# LiPoBattery.net
KiCad netlist of a schematic drawn in Altium Designer
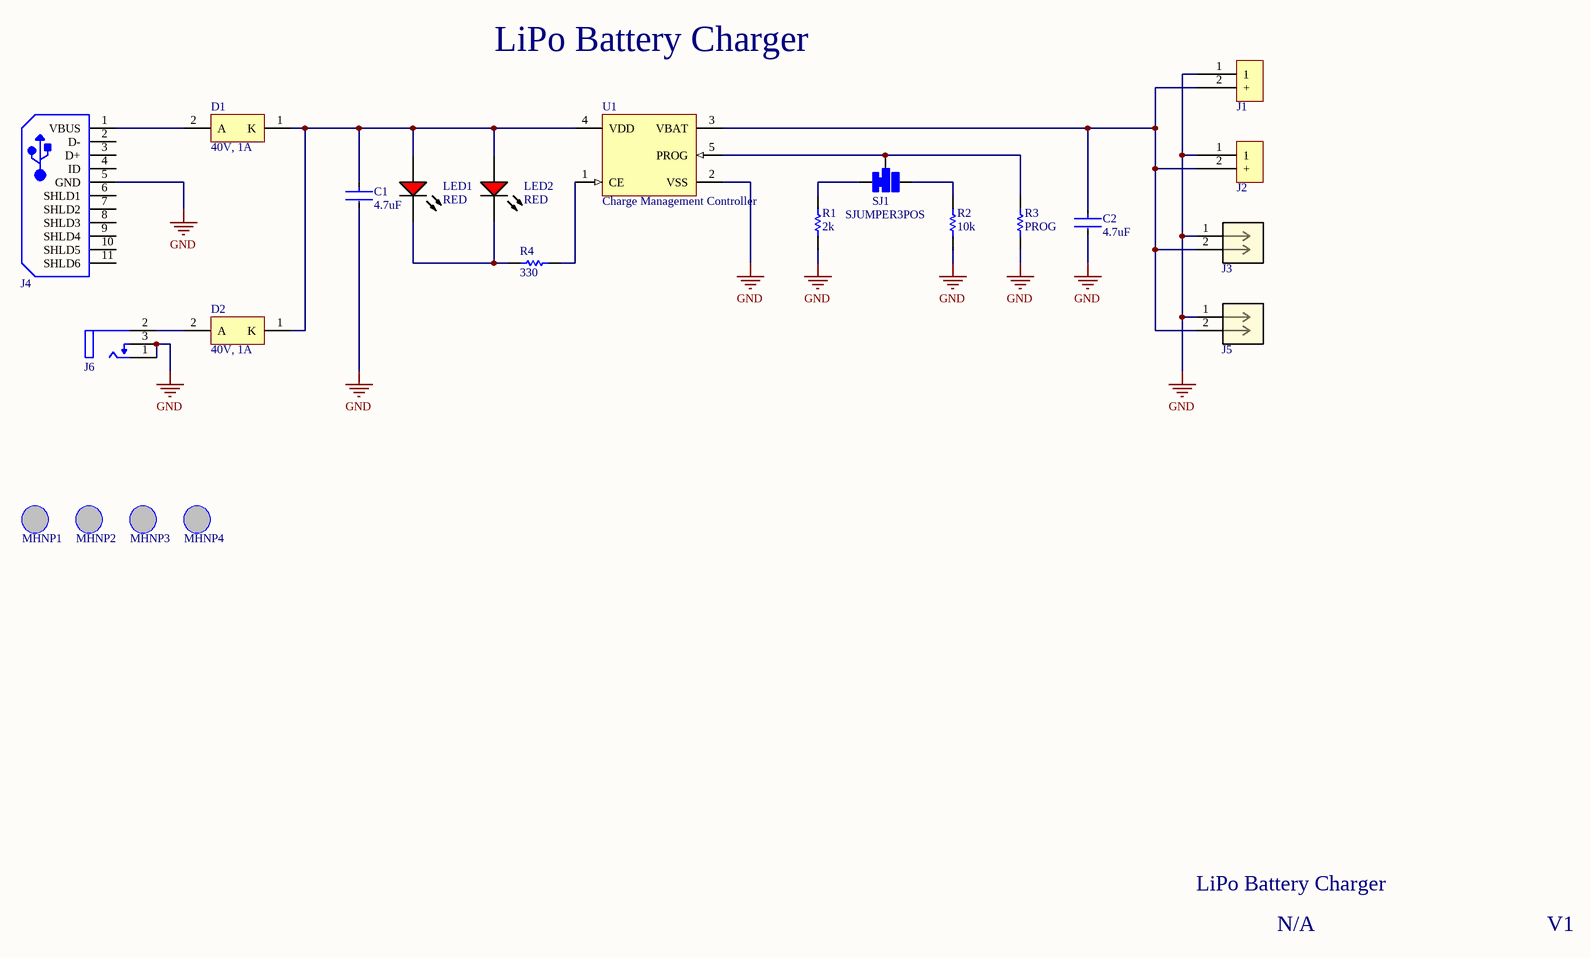
[diagram p0: LiPoBattery.SchDoc]

(export (version "E")
  (design (tool "Eeschema 10.0.6"))
  (components
    (comp (ref "C1")
      (value "4.7uF")
      (footprint "FP-CC0805-0_85-MFG")
      (description "4.7µF ±10% 6.3V Ceramic Capacitor X7R 0805 (2012 Metric)")
      (fields (field (name "MANUFACTURER") "Yageo") (field (name "TOLERANCE") "0.1"))
      (libsource (lib "LiPoBattery_A") (part "CAP CER 4.7UF 6.3V X7R 0805"))
    )
    (comp (ref "C2")
      (value "4.7uF")
      (footprint "FP-CC0805-0_85-MFG")
      (description "4.7µF ±10% 6.3V Ceramic Capacitor X7R 0805 (2012 Metric)")
      (fields (field (name "MANUFACTURER") "Yageo") (field (name "TOLERANCE") "0.1"))
      (libsource (lib "LiPoBattery_A") (part "CAP CER 4.7UF 6.3V X7R 0805"))
    )
    (comp (ref "D1")
      (value "40V, 1A")
      (footprint "ONSC-SMA-2-403D-02_V")
      (description "Schottky Power Rectifier, 2-Pin SMA, Pb-Free, Cut Tape, Diode Schottky 40V 1A Surface Mount SMA")
      (fields (field (name "PARTNUMBER") "MBRA140T3G") (field (name "MANUFACTURER") "ON Semiconductor"))
      (libsource (lib "LiPoBattery_A") (part "DIODE SCHOTTKY 40V 1A SMA"))
    )
    (comp (ref "D2")
      (value "40V, 1A")
      (footprint "ONSC-SMA-2-403D-02_V")
      (description "Schottky Power Rectifier, 2-Pin SMA, Pb-Free, Cut Tape, Diode Schottky 40V 1A Surface Mount SMA")
      (fields (field (name "PARTNUMBER") "MBRA140T3G") (field (name "MANUFACTURER") "ON Semiconductor"))
      (libsource (lib "LiPoBattery_A") (part "DIODE SCHOTTKY 40V 1A SMA"))
    )
    (comp (ref "J1")
      (value "CONN HEADER R/A 2POS 5.08MM")
      (footprint "1-179276-2")
      (description "Connector Header Through Hole, Right Angle 2 position 0.200\" (5.08mm)")
      (fields
        (field (name "MANUFACTURER") "TE Connectivity AMP Connectors")
        (field (name "MANUFACTURER PART NUMBER") "1-179276-2")
      )
      (libsource (lib "LiPoBattery_A") (part "CONN HEADER R/A 2POS 5.08MM"))
    )
    (comp (ref "J2")
      (value "CONN HEADER R/A 2POS 5.08MM")
      (footprint "1-179276-2")
      (description "Connector Header Through Hole, Right Angle 2 position 0.200\" (5.08mm)")
      (fields
        (field (name "MANUFACTURER") "TE Connectivity AMP Connectors")
        (field (name "MANUFACTURER PART NUMBER") "1-179276-2")
      )
      (libsource (lib "LiPoBattery_A") (part "CONN HEADER R/A 2POS 5.08MM"))
    )
    (comp (ref "J3")
      (value "2 POS VERT HEADER 0.100\"")
      (footprint "2Pins_AMP")
      (description "Connector Header Through Hole 2 position")
      (fields
        (field (name "MANUFACTURER PART NUMBER") "67997-402HLF")
        (field (name "MANUFACTURER") "Amphenol ICC (FCI)")
        (field (name "COPYRIGHT") "Copyright (C) 2018 Accelerated Designs. All rights reserved")
      )
      (libsource (lib "LiPoBattery_A") (part "CONN HEADER VERT 2POS 0.100{dblquote}"))
    )
    (comp (ref "J4")
      (value "47346-0001")
      (footprint "MOLX-47346-0001-5_V")
      (description "Micro-USB B Receptacle with Flange, -30 to 85 degC, 5-Pin SMD, RoHS, Tape and Reel")
      (fields (field (name "MANUFACTURER") "Molex"))
      (libsource (lib "LiPoBattery_A") (part "CONN RCPT USB2.0 MICRO B SMD R/A"))
    )
    (comp (ref "J5")
      (value "2 POS VERT HEADER 0.100\"")
      (footprint "2Pins_AMP")
      (description "Connector Header Through Hole 2 position")
      (fields
        (field (name "MANUFACTURER PART NUMBER") "67997-402HLF")
        (field (name "MANUFACTURER") "Amphenol ICC (FCI)")
        (field (name "COPYRIGHT") "Copyright (C) 2018 Accelerated Designs. All rights reserved")
      )
      (libsource (lib "LiPoBattery_A") (part "CONN HEADER VERT 2POS 0.100{dblquote}"))
    )
    (comp (ref "J6")
      (value "CONN PWR JACK 2.1X5.5MM SOLDER")
      (footprint "FP-RASM722PTR13X-MFG")
      (description "Power Barrel Connector Jack 2.10mm ID (0.083\"), 5.50mm OD (0.217\") Surface Mount, Right Angle")
      (fields
        (field (name "MANUFACTURER") "Switchcraft")
        (field (name "MANUFACTURER PART NUMBER") "RASM722PTR13X")
      )
      (libsource (lib "LiPoBattery_A") (part "CONN PWR JACK 2.1X5.5MM SOLDER"))
    )
    (comp (ref "LED1")
      (value "RED")
      (footprint "VISH-TLMS1000_V")
      (description "Low Current LED, 40 mW, 1.8 V, -40 to 100 degC, 2-Pin SMD (0603), RoHS, Tape and Reel")
      (fields
        (field (name "MANUFACTURER") "Vishay")
        (field (name "MANUFACTURER PART NUMBER") "TLMS1000-GS08")
      )
      (libsource (lib "LiPoBattery_A") (part "LED RED 0603 SMD"))
    )
    (comp (ref "LED2")
      (value "RED")
      (footprint "VISH-TLMS1000_V")
      (description "Low Current LED, 40 mW, 1.8 V, -40 to 100 degC, 2-Pin SMD (0603), RoHS, Tape and Reel")
      (fields
        (field (name "MANUFACTURER") "Vishay")
        (field (name "MANUFACTURER PART NUMBER") "TLMS1000-GS08")
      )
      (libsource (lib "LiPoBattery_A") (part "LED RED 0603 SMD"))
    )
    (comp (ref "MHNP1")
      (value "Mounting Hole Non-Plated 3.2mm")
      (footprint "MTHNP3P2MM")
      (description "Mounting Hole Non-Plated 3.2 mm drill hole")
      (libsource (lib "LiPoBattery_A") (part "MTHNP3P2MM"))
    )
    (comp (ref "MHNP2")
      (value "Mounting Hole Non-Plated 3.2mm")
      (footprint "MTHNP3P2MM")
      (description "Mounting Hole Non-Plated 3.2 mm drill hole")
      (libsource (lib "LiPoBattery_A") (part "MTHNP3P2MM"))
    )
    (comp (ref "MHNP3")
      (value "Mounting Hole Non-Plated 3.2mm")
      (footprint "MTHNP3P2MM")
      (description "Mounting Hole Non-Plated 3.2 mm drill hole")
      (libsource (lib "LiPoBattery_A") (part "MTHNP3P2MM"))
    )
    (comp (ref "MHNP4")
      (value "Mounting Hole Non-Plated 3.2mm")
      (footprint "MTHNP3P2MM")
      (description "Mounting Hole Non-Plated 3.2 mm drill hole")
      (libsource (lib "LiPoBattery_A") (part "MTHNP3P2MM"))
    )
    (comp (ref "R1")
      (value "2k")
      (footprint "RESC2013X70X40ML20T20")
      (description "2 kOhms ±5% 0.125W, 1/8W Chip Resistor 0805 (2012 Metric) Automotive AEC-Q200 Thick Film")
      (fields
        (field (name "MANUFACTURER") "Panasonic")
        (field (name "MANUFACTURER PART NUMBER") "ERJ-6GEYJ202V")
      )
      (libsource (lib "LiPoBattery_A") (part "RES SMD 2K OHM 5% 1/8W 0805"))
    )
    (comp (ref "R2")
      (value "10k")
      (footprint "RESC2013X70X40ML20T20")
      (description "10 kOhms ±1% 0.125W, 1/8W Chip Resistor 0805 (2012 Metric) Automotive AEC-Q200 Thick Film")
      (fields
        (field (name "MANUFACTURER") "Panasonic")
        (field (name "MANUFACTURER PART NUMBER") "ERJ-6ENF1002V")
      )
      (libsource (lib "LiPoBattery_A") (part "RES SMD 10K OHM 1% 1/8W 0805"))
    )
    (comp (ref "R3")
      (value "PROG")
      (footprint "VISH-A1-2_V2")
      (fields
        (field (name "TOLERANCE") "+/-5%")
        (field (name "POWER") "2 W")
        (field (name "PARTNUMBER") "PR02000206202JA100")
      )
      (libsource (lib "LiPoBattery_A") (part "RES 62K OHM 2W 5% AXIAL"))
    )
    (comp (ref "R4")
      (value "330")
      (footprint "RESC2013X50X30NL20T20")
      (description "330 Ohms ±1% 0.125W, 1/8W Chip Resistor 0805 (2012 Metric) Automotive AEC-Q200 Thick Film")
      (fields
        (field (name "MANUFACTURER") "Vishay")
        (field (name "MANUFACTURER PART NUMBER") "CRCW0805330RFKEA")
      )
      (libsource (lib "LiPoBattery_A") (part "RES SMD 330 OHM 1% 1/8W 0805"))
    )
    (comp (ref "SJ1")
      (value "SJUMPER3POS")
      (footprint "SJUMPER3POS-Footprint-1")
      (description "Solder jumper 3 pads and pins")
      (libsource (lib "LiPoBattery_A") (part "SJUMPER3POS"))
    )
    (comp (ref "U1")
      (value "Charge Management Controller")
      (footprint "SOT-23-OT5_M")
      (fields
        (field (name "MANUFACTURER") "Microchip")
        (field (name "MANUFACTURER PART NUMBER") "MCP73811T-420I/OT")
      )
      (libsource (lib "LiPoBattery_A") (part "IC LI-ION/LI-POLY CTRLR SOT23-5"))
    )
  )
  (nets
    (net (code "1") (name "GND") (class "Default")
      (node (ref "C1") (pin "2") (pinfunction "2_2") (pintype "passive"))
      (node (ref "C2") (pin "2") (pinfunction "2_2") (pintype "passive"))
      (node (ref "J1") (pin "1") (pinfunction "1_1") (pintype "passive"))
      (node (ref "J2") (pin "1") (pinfunction "1_1") (pintype "passive"))
      (node (ref "J3") (pin "1") (pinfunction "1_1") (pintype "passive"))
      (node (ref "J4") (pin "5") (pinfunction "GND_5") (pintype "passive"))
      (node (ref "J5") (pin "1") (pinfunction "1_1") (pintype "passive"))
      (node (ref "J6") (pin "1") (pinfunction "TIP_TERMINAL(CENTER_PIN)_1") (pintype "passive"))
      (node (ref "J6") (pin "3") (pinfunction "SHUNT_TERMINAL_3") (pintype "passive"))
      (node (ref "R1") (pin "1") (pinfunction "1_1") (pintype "passive"))
      (node (ref "R2") (pin "1") (pinfunction "1_1") (pintype "passive"))
      (node (ref "R3") (pin "1") (pinfunction "1_1") (pintype "passive"))
      (node (ref "U1") (pin "2") (pinfunction "VSS_2") (pintype "power_in"))
    )
    (net (code "2") (name "Net-(D1-A)") (class "Default")
      (node (ref "D1") (pin "2") (pinfunction "A_2") (pintype "passive"))
      (node (ref "J4") (pin "1") (pinfunction "VBUS_1") (pintype "passive"))
    )
    (net (code "3") (name "Net-(D1-K)") (class "Default")
      (node (ref "C1") (pin "1") (pinfunction "1_1") (pintype "passive"))
      (node (ref "D1") (pin "1") (pinfunction "K_1") (pintype "passive"))
      (node (ref "D2") (pin "1") (pinfunction "K_1") (pintype "passive"))
      (node (ref "LED1") (pin "1") (pinfunction "A_1") (pintype "passive"))
      (node (ref "LED2") (pin "1") (pinfunction "A_1") (pintype "passive"))
      (node (ref "U1") (pin "4") (pinfunction "VDD_4") (pintype "power_in"))
    )
    (net (code "4") (name "Net-(D2-A)") (class "Default")
      (node (ref "D2") (pin "2") (pinfunction "A_2") (pintype "passive"))
      (node (ref "J6") (pin "2") (pinfunction "SLEEVE_TERMINAL_2") (pintype "passive"))
    )
    (net (code "5") (name "Net-(J1-+)") (class "Default")
      (node (ref "C2") (pin "1") (pinfunction "1_1") (pintype "passive"))
      (node (ref "J1") (pin "2") (pinfunction "+_2") (pintype "passive"))
      (node (ref "J2") (pin "2") (pinfunction "+_2") (pintype "passive"))
      (node (ref "J3") (pin "2") (pinfunction "2_2") (pintype "passive"))
      (node (ref "J5") (pin "2") (pinfunction "2_2") (pintype "passive"))
      (node (ref "U1") (pin "3") (pinfunction "VBAT_3") (pintype "power_in"))
    )
    (net (code "6") (name "Net-(LED1-K)") (class "Default")
      (node (ref "LED1") (pin "2") (pinfunction "K_2") (pintype "passive"))
      (node (ref "LED2") (pin "2") (pinfunction "K_2") (pintype "passive"))
      (node (ref "R4") (pin "1") (pinfunction "1_1") (pintype "passive"))
    )
    (net (code "7") (name "Net-(R1-Pad2)") (class "Default")
      (node (ref "R1") (pin "2") (pinfunction "2_2") (pintype "passive"))
      (node (ref "SJ1") (pin "1") (pinfunction "1_1") (pintype "passive"))
    )
    (net (code "8") (name "Net-(R2-Pad2)") (class "Default")
      (node (ref "R2") (pin "2") (pinfunction "2_2") (pintype "passive"))
      (node (ref "SJ1") (pin "3") (pinfunction "3_3") (pintype "passive"))
    )
    (net (code "9") (name "Net-(U1-CE)") (class "Default")
      (node (ref "R4") (pin "2") (pinfunction "2_2") (pintype "passive"))
      (node (ref "U1") (pin "1") (pinfunction "CE_1") (pintype "input"))
    )
    (net (code "10") (name "Net-(U1-PROG)") (class "Default")
      (node (ref "R3") (pin "2") (pinfunction "2_2") (pintype "passive"))
      (node (ref "SJ1") (pin "2") (pinfunction "2_2") (pintype "passive"))
      (node (ref "U1") (pin "5") (pinfunction "PROG_5") (pintype "input"))
    )
    (net (code "11") (name "unconnected-(J4-D+-Pad3)") (class "Default")
      (node (ref "J4") (pin "3") (pinfunction "D+_3") (pintype "passive"))
    )
    (net (code "12") (name "unconnected-(J4-D--Pad2)") (class "Default")
      (node (ref "J4") (pin "2") (pinfunction "D-_2") (pintype "passive"))
    )
    (net (code "13") (name "unconnected-(J4-ID-Pad4)") (class "Default")
      (node (ref "J4") (pin "4") (pinfunction "ID_4") (pintype "passive"))
    )
    (net (code "14") (name "unconnected-(J4-SHLD1-Pad6)") (class "Default")
      (node (ref "J4") (pin "6") (pinfunction "SHLD1_6") (pintype "passive"))
    )
    (net (code "15") (name "unconnected-(J4-SHLD2-Pad7)") (class "Default")
      (node (ref "J4") (pin "7") (pinfunction "SHLD2_7") (pintype "passive"))
    )
    (net (code "16") (name "unconnected-(J4-SHLD3-Pad8)") (class "Default")
      (node (ref "J4") (pin "8") (pinfunction "SHLD3_8") (pintype "passive"))
    )
    (net (code "17") (name "unconnected-(J4-SHLD4-Pad9)") (class "Default")
      (node (ref "J4") (pin "9") (pinfunction "SHLD4_9") (pintype "passive"))
    )
    (net (code "18") (name "unconnected-(J4-SHLD5-Pad10)") (class "Default")
      (node (ref "J4") (pin "10") (pinfunction "SHLD5_10") (pintype "passive"))
    )
    (net (code "19") (name "unconnected-(J4-SHLD6-Pad11)") (class "Default")
      (node (ref "J4") (pin "11") (pinfunction "SHLD6_11") (pintype "passive"))
    )
  )
)
